# 20200614.net
KiCad netlist of a schematic drawn in Altium Designer
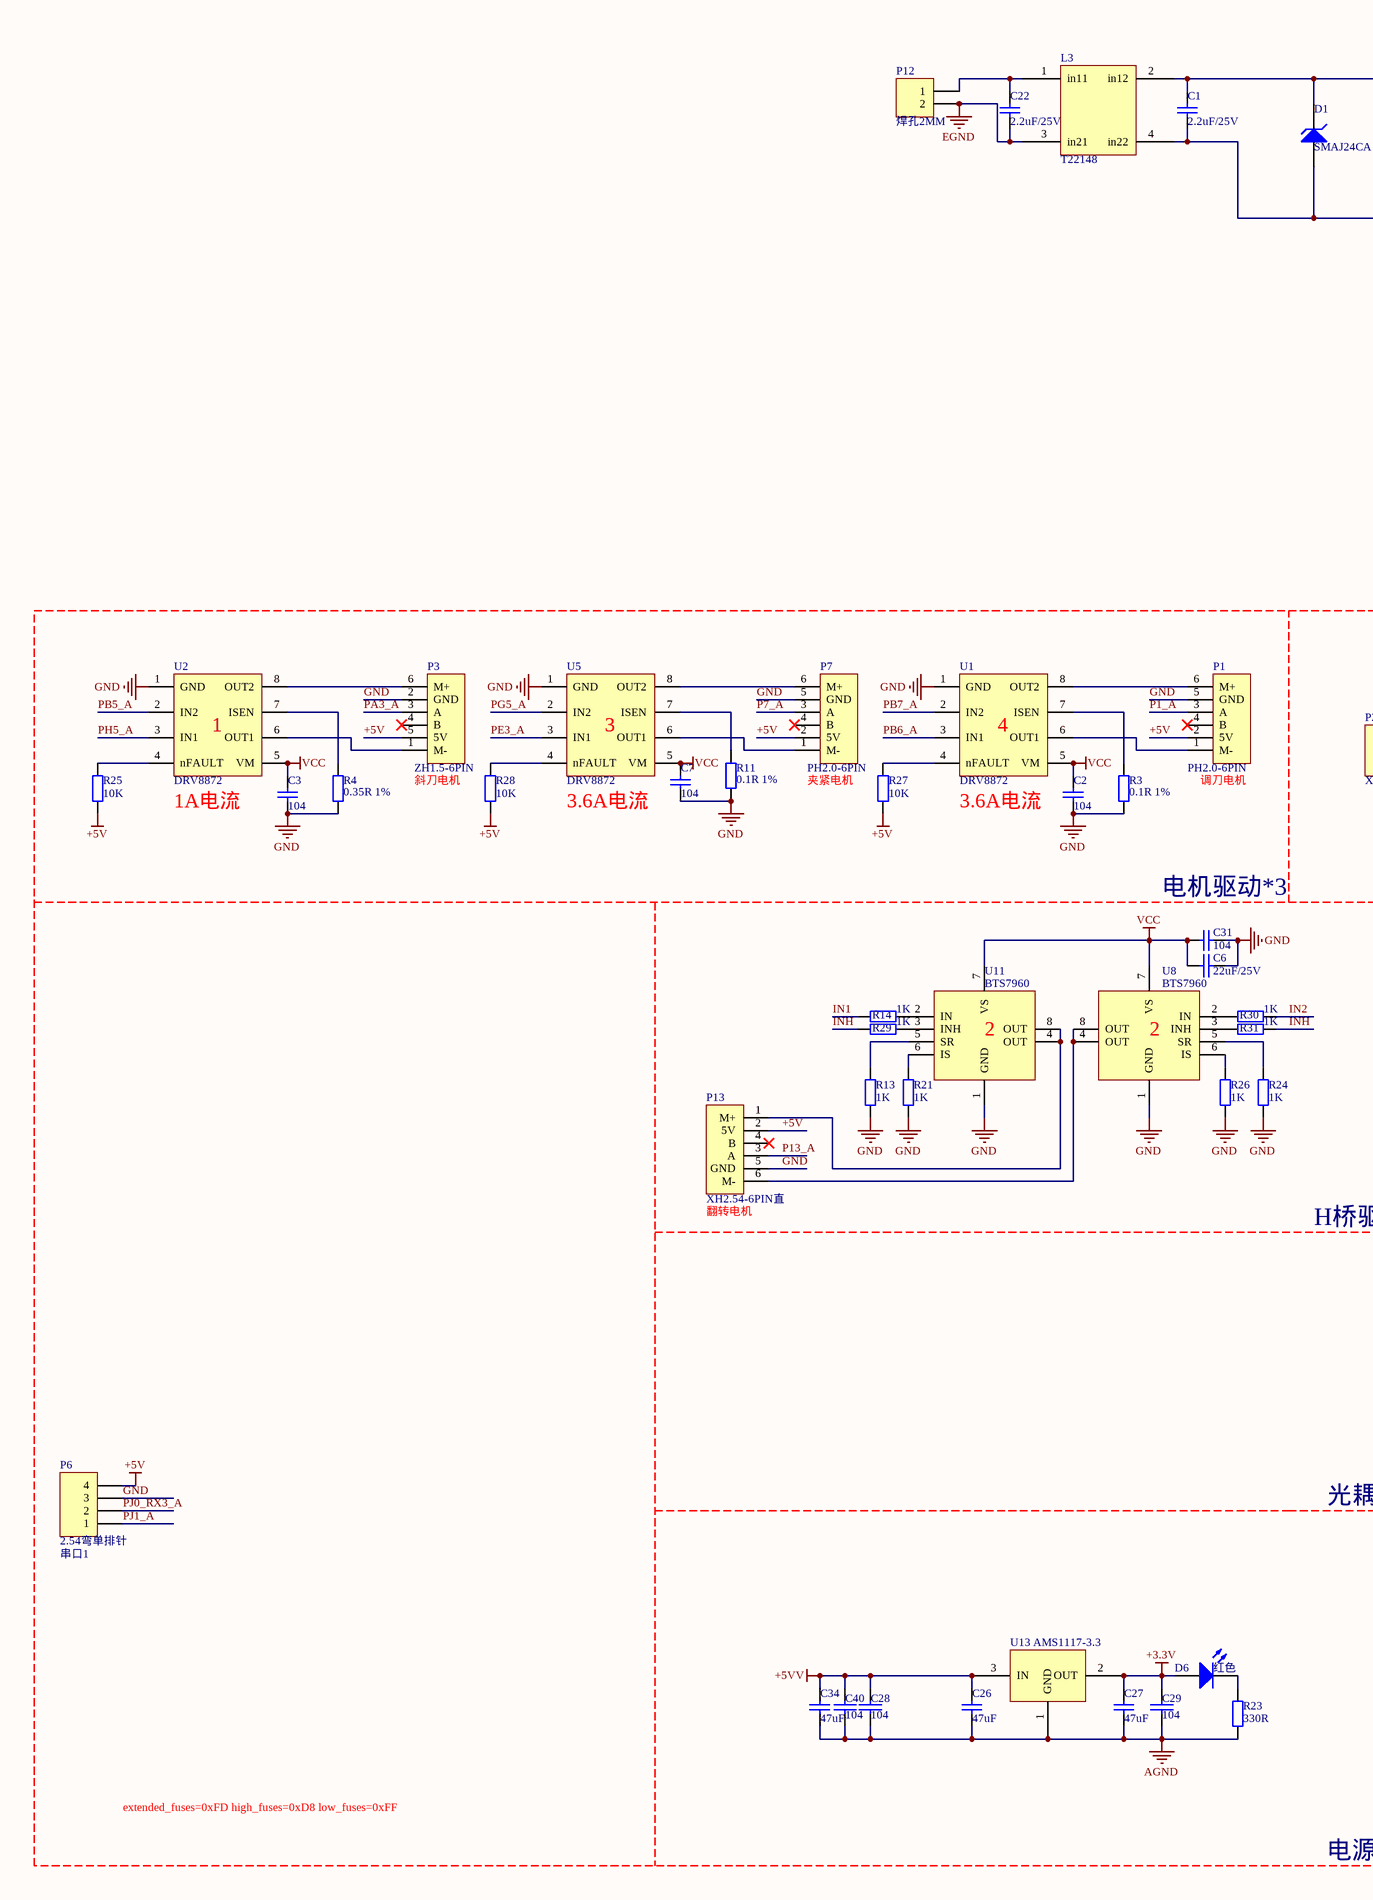
[diagram p0: 剥皮器20200614.SCHDOC, left]
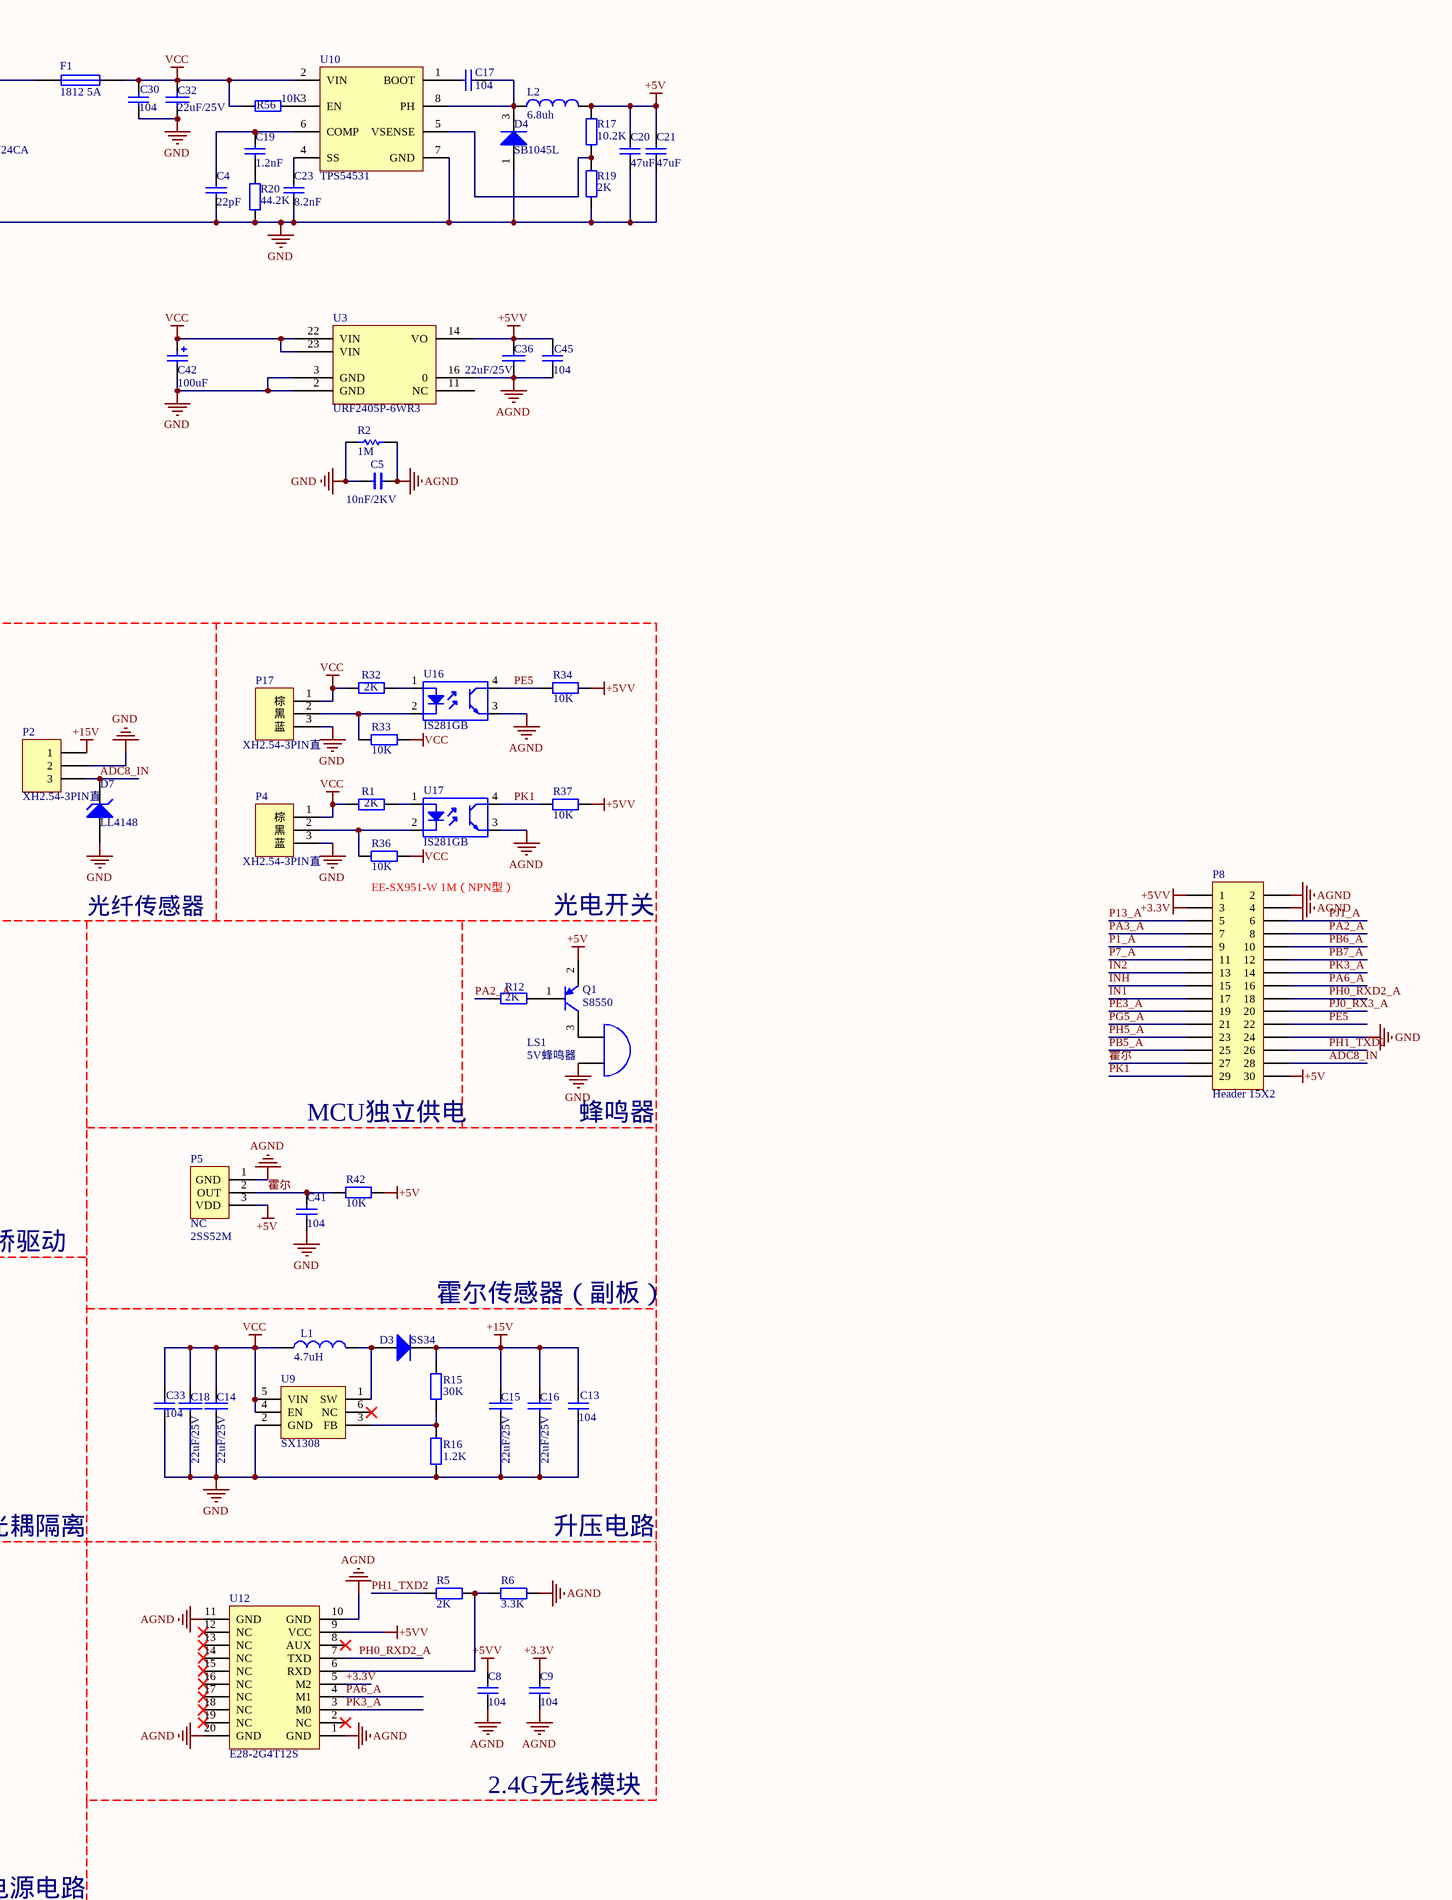
[diagram p1: 剥皮器20200614.SCHDOC, right]

(export (version "E")
  (design (tool "Eeschema 10.0.6"))
  (components
    (comp (ref "C1")
      (value "2.2uF/25V")
      (footprint "0805-C")
      (description "Capacitor")
      (fields (field (name "PUBLISHER") "Altium Limited"))
      (libsource (lib "Miscellaneous Devices") (part "Cap"))
    )
    (comp (ref "C2")
      (value "104")
      (footprint "0805-C")
      (description "Capacitor")
      (fields (field (name "PUBLISHER") "Altium Limited"))
      (libsource (lib "Miscellaneous Devices") (part "Cap"))
    )
    (comp (ref "C3")
      (value "104")
      (footprint "0805-C")
      (description "Capacitor")
      (fields (field (name "PUBLISHER") "Altium Limited"))
      (libsource (lib "Miscellaneous Devices") (part "Cap"))
    )
    (comp (ref "C4")
      (value "22pF")
      (footprint "0805-C")
      (description "Capacitor")
      (fields (field (name "PUBLISHER") "Altium Limited"))
      (libsource (lib "Miscellaneous Devices") (part "Cap"))
    )
    (comp (ref "C5")
      (value "10nF/2KV")
      (footprint "1206C")
      (description "C")
      (libsource (lib "Schlib_20110825") (part "C"))
    )
    (comp (ref "C6")
      (value "22uF/25V")
      (footprint "1206C")
      (description "Capacitor")
      (libsource (lib "*") (part "CAP"))
    )
    (comp (ref "C7")
      (value "104")
      (footprint "0805-C")
      (description "Capacitor")
      (fields (field (name "PUBLISHER") "Altium Limited"))
      (libsource (lib "Miscellaneous Devices") (part "Cap"))
    )
    (comp (ref "C8")
      (value "104")
      (footprint "0805-C")
      (description "Capacitor")
      (fields (field (name "PUBLISHER") "Altium Limited"))
      (libsource (lib "Miscellaneous Devices") (part "Cap"))
    )
    (comp (ref "C9")
      (value "104")
      (footprint "0805-C")
      (description "Capacitor")
      (fields (field (name "PUBLISHER") "Altium Limited"))
      (libsource (lib "Miscellaneous Devices") (part "Cap"))
    )
    (comp (ref "C13")
      (value "104")
      (footprint "0805-C")
      (description "Capacitor")
      (fields (field (name "PUBLISHER") "Altium Limited"))
      (libsource (lib "Miscellaneous Devices") (part "Cap"))
    )
    (comp (ref "C14")
      (value "22uF/25V")
      (footprint "1206-C")
      (description "Capacitor")
      (libsource (lib "*") (part "CAP"))
    )
    (comp (ref "C15")
      (value "22uF/25V")
      (footprint "1206-C")
      (description "Capacitor")
      (libsource (lib "*") (part "CAP"))
    )
    (comp (ref "C16")
      (value "22uF/25V")
      (footprint "1206-C")
      (description "Capacitor")
      (libsource (lib "*") (part "CAP"))
    )
    (comp (ref "C17")
      (value "104")
      (footprint "0805-C")
      (description "Capacitor")
      (fields (field (name "PUBLISHER") "Altium Limited"))
      (libsource (lib "Miscellaneous Devices") (part "Cap"))
    )
    (comp (ref "C18")
      (value "22uF/25V")
      (footprint "1206-C")
      (description "Capacitor")
      (libsource (lib "*") (part "CAP"))
    )
    (comp (ref "C19")
      (value "1.2nF")
      (footprint "0805-C")
      (description "Capacitor")
      (fields (field (name "PUBLISHER") "Altium Limited"))
      (libsource (lib "Miscellaneous Devices") (part "Cap"))
    )
    (comp (ref "C20")
      (value "47uF")
      (footprint "0805-C")
      (description "Capacitor")
      (fields (field (name "PUBLISHER") "Altium Limited"))
      (libsource (lib "Miscellaneous Devices") (part "Cap"))
    )
    (comp (ref "C21")
      (value "47uF")
      (footprint "0805-C")
      (description "Capacitor")
      (fields (field (name "PUBLISHER") "Altium Limited"))
      (libsource (lib "Miscellaneous Devices") (part "Cap"))
    )
    (comp (ref "C22")
      (value "2.2uF/25V")
      (footprint "0805-C")
      (description "Capacitor")
      (fields (field (name "PUBLISHER") "Altium Limited"))
      (libsource (lib "Miscellaneous Devices") (part "Cap"))
    )
    (comp (ref "C23")
      (value "8.2nF")
      (footprint "0805-C")
      (description "Capacitor")
      (fields (field (name "PUBLISHER") "Altium Limited"))
      (libsource (lib "Miscellaneous Devices") (part "Cap"))
    )
    (comp (ref "C26")
      (value "47uF")
      (footprint "0805-C")
      (description "Capacitor")
      (fields (field (name "PUBLISHER") "Altium Limited"))
      (libsource (lib "Miscellaneous Devices") (part "Cap"))
    )
    (comp (ref "C27")
      (value "47uF")
      (footprint "0805-C")
      (description "Capacitor")
      (fields (field (name "PUBLISHER") "Altium Limited"))
      (libsource (lib "Miscellaneous Devices") (part "Cap"))
    )
    (comp (ref "C28")
      (value "104")
      (footprint "0805-C")
      (description "Capacitor")
      (libsource (lib "*") (part "CAP"))
    )
    (comp (ref "C29")
      (value "104")
      (footprint "0805-C")
      (description "Capacitor")
      (libsource (lib "*") (part "CAP"))
    )
    (comp (ref "C30")
      (value "104")
      (footprint "0805-C")
      (description "Capacitor")
      (fields (field (name "PUBLISHER") "Altium Limited"))
      (libsource (lib "Miscellaneous Devices") (part "Cap"))
    )
    (comp (ref "C31")
      (value "104")
      (footprint "0805-C")
      (description "Capacitor")
      (fields (field (name "PUBLISHER") "Altium Limited"))
      (libsource (lib "Miscellaneous Devices") (part "Cap"))
    )
    (comp (ref "C32")
      (value "22uF/25V")
      (footprint "1206-C")
      (description "Capacitor")
      (libsource (lib "*") (part "CAP"))
    )
    (comp (ref "C33")
      (value "104")
      (footprint "0805-C")
      (description "Capacitor")
      (fields (field (name "PUBLISHER") "Altium Limited"))
      (libsource (lib "Miscellaneous Devices") (part "Cap"))
    )
    (comp (ref "C34")
      (value "47uF")
      (footprint "0805-C")
      (description "Capacitor")
      (fields (field (name "PUBLISHER") "Altium Limited"))
      (libsource (lib "Miscellaneous Devices") (part "Cap"))
    )
    (comp (ref "C36")
      (value "22uF/25V")
      (footprint "1206-C")
      (description "Capacitor")
      (libsource (lib "*") (part "CAP"))
    )
    (comp (ref "C40")
      (value "104")
      (footprint "0805-C")
      (description "Capacitor")
      (libsource (lib "*") (part "CAP"))
    )
    (comp (ref "C41")
      (value "104")
      (footprint "0805-C")
      (description "Capacitor")
      (fields (field (name "PUBLISHER") "Altium Limited"))
      (libsource (lib "Miscellaneous Devices") (part "Cap"))
    )
    (comp (ref "C42")
      (value "100uF")
      (footprint "LC-CASE-C_6032")
      (description "Polarized Capacitor (Axial)")
      (fields (field (name "PUBLISHER") "Altium Limited"))
      (libsource (lib "Miscellaneous Devices") (part "Cap Pol2"))
    )
    (comp (ref "C45")
      (value "104")
      (footprint "0805-C")
      (description "Capacitor")
      (fields (field (name "PUBLISHER") "Altium Limited"))
      (libsource (lib "Miscellaneous Devices") (part "Cap"))
    )
    (comp (ref "D1")
      (value "SMAJ24CA")
      (footprint "sma")
      (description "Zener Diode")
      (fields (field (name "PUBLISHER") "Altium Limited"))
      (libsource (lib "Miscellaneous Devices") (part "D Zener"))
    )
    (comp (ref "D3")
      (value "SS34")
      (footprint "SMA - JW")
      (description "1 Amp General Purpose Rectifier")
      (fields (field (name "PUBLISHER") "Altium Limited"))
      (libsource (lib "Miscellaneous Devices") (part "Diode 1N4007"))
    )
    (comp (ref "D4")
      (value "SB1045L")
      (footprint "TO-277")
      (description "1 Amp General Purpose Rectifier")
      (fields (field (name "PUBLISHER") "Altium Limited"))
      (libsource (lib "Miscellaneous Devices") (part "Diode 1N4001"))
    )
    (comp (ref "D6")
      (value "红色")
      (footprint "0805-LED")
      (description "Typical INFRARED GaAs LED")
      (fields (field (name "PUBLISHER") "Altium Limited"))
      (libsource (lib "Miscellaneous Devices") (part "LED0"))
    )
    (comp (ref "D7")
      (value "LL4148")
      (footprint "LC-LL-34")
      (description "Zener Diode")
      (fields (field (name "PUBLISHER") "Altium Limited"))
      (libsource (lib "Miscellaneous Devices") (part "D Zener"))
    )
    (comp (ref "F1")
      (value "1812 5A")
      (footprint "LC-1812_R")
      (description "Fuse")
      (fields (field (name "PUBLISHER") "Altium Limited"))
      (libsource (lib "Miscellaneous Devices") (part "Fuse 1"))
    )
    (comp (ref "L1")
      (value "4.7uH")
      (footprint "7*7*4电感")
      (description "Inductor")
      (fields (field (name "PUBLISHER") "Altium Limited"))
      (libsource (lib "Miscellaneous Devices") (part "Inductor"))
    )
    (comp (ref "L2")
      (value "6.8uh")
      (footprint "7*7*4电感")
      (description "Inductor")
      (fields (field (name "PUBLISHER") "Altium Limited"))
      (libsource (lib "Miscellaneous Devices") (part "Inductor"))
    )
    (comp (ref "L3") (value "T22148") (footprint "T181007") (libsource (lib "Schlib_20110825") (part "共模电感")))
    (comp (ref "LS1")
      (value "5V蜂鸣器")
      (footprint "蜂鸣器0905")
      (description "Electrical Bell")
      (fields (field (name "PUBLISHER") "Altium Limited"))
      (libsource (lib "Miscellaneous Devices") (part "Bell"))
    )
    (comp (ref "P1")
      (value "PH2.0-6PIN")
      (footprint "PH2.0-6PIN")
      (description "Header, 6-Pin")
      (fields (field (name "PUBLISHER") "Altium Limited"))
      (libsource (lib "") (part "Header 6_2"))
    )
    (comp (ref "P2")
      (value "XH2.54-3PIN直")
      (footprint "XH2.54-3PIN直")
      (description "Header, 3-Pin")
      (fields (field (name "PUBLISHER") "Altium Limited"))
      (libsource (lib "Miscellaneous Connectors") (part "Header 3"))
    )
    (comp (ref "P3")
      (value "ZH1.5-6PIN")
      (footprint "ZH1.5-6PIN")
      (description "Header, 6-Pin")
      (fields (field (name "PUBLISHER") "Altium Limited"))
      (libsource (lib "") (part "Header 6_1"))
    )
    (comp (ref "P4")
      (value "XH2.54-3PIN直")
      (footprint "XH2.54-3PIN直")
      (description "Header, 3-Pin")
      (fields (field (name "PUBLISHER") "Altium Limited"))
      (libsource (lib "") (part "Header 3_1"))
    )
    (comp (ref "P5")
      (value "NC")
      (footprint "2SS52M")
      (description "Header, 3-Pin")
      (fields (field (name "PUBLISHER") "2SS52M"))
      (libsource (lib "") (part "Header 3_2"))
    )
    (comp (ref "P6")
      (value "2.54弯单排针")
      (footprint "HDR1X4H")
      (description "Header, 4-Pin")
      (fields (field (name "ALTIUM_UNNAMED_1") "串口1") (field (name "PUBLISHER") "Altium Limited"))
      (libsource (lib "Miscellaneous Connectors") (part "Header 4"))
    )
    (comp (ref "P7")
      (value "PH2.0-6PIN")
      (footprint "PH2.0-6PIN")
      (description "Header, 6-Pin")
      (fields (field (name "PUBLISHER") "Altium Limited"))
      (libsource (lib "") (part "Header 6_2"))
    )
    (comp (ref "P8")
      (value "Header 15X2")
      (footprint "SIP15-1.27")
      (description "Header, 15-Pin, Dual row")
      (fields (field (name "PUBLISHER") "Altium Limited"))
      (libsource (lib "Miscellaneous Connectors") (part "Header 15X2"))
    )
    (comp (ref "P12")
      (value "焊孔2MM")
      (footprint "HDR1X2")
      (description "Header, 2-Pin")
      (fields (field (name "PUBLISHER") "Altium Limited"))
      (libsource (lib "Miscellaneous Connectors") (part "Header 2"))
    )
    (comp (ref "P13")
      (value "XH2.54-6PIN直")
      (footprint "XH2.54-6PIN直")
      (description "Header, 6-Pin")
      (fields (field (name "PUBLISHER") "Altium Limited"))
      (libsource (lib "Miscellaneous Connectors") (part "Header 6"))
    )
    (comp (ref "P17")
      (value "XH2.54-3PIN直")
      (footprint "XH2.54-3PIN直")
      (description "Header, 3-Pin")
      (fields (field (name "PUBLISHER") "Altium Limited"))
      (libsource (lib "") (part "Header 3_1"))
    )
    (comp (ref "Q1")
      (value "S8550")
      (footprint "SOT--23")
      (description "PNP General Purpose Amplifier")
      (fields (field (name "PUBLISHER") "Altium Limited"))
      (libsource (lib "Miscellaneous Devices") (part "2N3906"))
    )
    (comp (ref "R1")
      (value "2K")
      (footprint "0805-R")
      (description "Resistor")
      (fields (field (name "PUBLISHER") "Altium Limited"))
      (libsource (lib "Miscellaneous Devices") (part "Res2"))
    )
    (comp (ref "R2")
      (value "1M")
      (footprint "2512R")
      (description "Resistor")
      (fields (field (name "PUBLISHER") "Altium Limited"))
      (libsource (lib "Miscellaneous Devices") (part "Res1"))
    )
    (comp (ref "R3")
      (value "0.1R 1%")
      (footprint "2512-R")
      (description "Resistor")
      (fields (field (name "PUBLISHER") "Altium Limited"))
      (libsource (lib "") (part "Res2_2"))
    )
    (comp (ref "R4")
      (value "0.35R 1%")
      (footprint "2512-R")
      (description "Resistor")
      (fields (field (name "PUBLISHER") "Altium Limited"))
      (libsource (lib "") (part "Res2_2"))
    )
    (comp (ref "R5")
      (value "2K")
      (footprint "0805-R")
      (description "Resistor")
      (fields (field (name "PUBLISHER") "Altium Limited"))
      (libsource (lib "Miscellaneous Devices") (part "Res2"))
    )
    (comp (ref "R6")
      (value "3.3K")
      (footprint "0805-R")
      (description "Resistor")
      (fields (field (name "PUBLISHER") "Altium Limited"))
      (libsource (lib "Miscellaneous Devices") (part "Res2"))
    )
    (comp (ref "R11")
      (value "0.1R 1%")
      (footprint "2512-R")
      (description "Resistor")
      (fields (field (name "PUBLISHER") "Altium Limited"))
      (libsource (lib "") (part "Res2_2"))
    )
    (comp (ref "R12")
      (value "2K")
      (footprint "0805-R")
      (description "Resistor")
      (fields (field (name "PUBLISHER") "Altium Limited"))
      (libsource (lib "") (part "Res2_1"))
    )
    (comp (ref "R13")
      (value "1K")
      (footprint "0805-R")
      (description "Resistor")
      (fields (field (name "PUBLISHER") "Altium Limited"))
      (libsource (lib "") (part "Res2_2"))
    )
    (comp (ref "R14")
      (value "1K")
      (footprint "0805-R")
      (description "Resistor")
      (fields (field (name "PUBLISHER") "Altium Limited"))
      (libsource (lib "") (part "Res2_1"))
    )
    (comp (ref "R15")
      (value "30K")
      (footprint "0805-R")
      (description "Resistor")
      (fields (field (name "PUBLISHER") "Altium Limited"))
      (libsource (lib "") (part "Res2_3"))
    )
    (comp (ref "R16")
      (value "1.2K")
      (footprint "0805-R")
      (description "Resistor")
      (fields (field (name "PUBLISHER") "Altium Limited"))
      (libsource (lib "") (part "Res2_3"))
    )
    (comp (ref "R17")
      (value "10.2K")
      (footprint "0805-R")
      (description "Resistor")
      (fields (field (name "PUBLISHER") "Altium Limited"))
      (libsource (lib "") (part "Res2_2"))
    )
    (comp (ref "R19")
      (value "2K")
      (footprint "0805-R")
      (description "Resistor")
      (fields (field (name "PUBLISHER") "Altium Limited"))
      (libsource (lib "") (part "Res2_2"))
    )
    (comp (ref "R20")
      (value "44.2K")
      (footprint "0805-R")
      (description "Resistor")
      (fields (field (name "PUBLISHER") "Altium Limited"))
      (libsource (lib "") (part "Res2_2"))
    )
    (comp (ref "R21")
      (value "1K")
      (footprint "0805-R")
      (description "Resistor")
      (fields (field (name "PUBLISHER") "Altium Limited"))
      (libsource (lib "") (part "Res2_2"))
    )
    (comp (ref "R23")
      (value "330R")
      (footprint "0805-R")
      (description "Resistor")
      (fields (field (name "PUBLISHER") "Altium Limited"))
      (libsource (lib "") (part "Res2_3"))
    )
    (comp (ref "R24")
      (value "1K")
      (footprint "0805-R")
      (description "Resistor")
      (fields (field (name "PUBLISHER") "Altium Limited"))
      (libsource (lib "Miscellaneous Devices") (part "Res2"))
    )
    (comp (ref "R25")
      (value "10K")
      (footprint "0805-R")
      (description "Resistor")
      (fields (field (name "PUBLISHER") "Altium Limited"))
      (libsource (lib "") (part "Res2_2"))
    )
    (comp (ref "R26")
      (value "1K")
      (footprint "0805-R")
      (description "Resistor")
      (fields (field (name "PUBLISHER") "Altium Limited"))
      (libsource (lib "Miscellaneous Devices") (part "Res2"))
    )
    (comp (ref "R27")
      (value "10K")
      (footprint "0805-R")
      (description "Resistor")
      (fields (field (name "PUBLISHER") "Altium Limited"))
      (libsource (lib "") (part "Res2_2"))
    )
    (comp (ref "R28")
      (value "10K")
      (footprint "0805-R")
      (description "Resistor")
      (fields (field (name "PUBLISHER") "Altium Limited"))
      (libsource (lib "") (part "Res2_2"))
    )
    (comp (ref "R29")
      (value "1K")
      (footprint "0805-R")
      (description "Resistor")
      (fields (field (name "PUBLISHER") "Altium Limited"))
      (libsource (lib "") (part "Res2_1"))
    )
    (comp (ref "R30")
      (value "1K")
      (footprint "0805-R")
      (description "Resistor")
      (fields (field (name "PUBLISHER") "Altium Limited"))
      (libsource (lib "") (part "Res2_1"))
    )
    (comp (ref "R31")
      (value "1K")
      (footprint "0805-R")
      (description "Resistor")
      (fields (field (name "PUBLISHER") "Altium Limited"))
      (libsource (lib "") (part "Res2_1"))
    )
    (comp (ref "R32")
      (value "2K")
      (footprint "0805-R")
      (description "Resistor")
      (fields (field (name "PUBLISHER") "Altium Limited"))
      (libsource (lib "Miscellaneous Devices") (part "Res2"))
    )
    (comp (ref "R33")
      (value "10K")
      (footprint "0805-R")
      (description "Resistor")
      (fields (field (name "PUBLISHER") "Altium Limited"))
      (libsource (lib "") (part "Res2_1"))
    )
    (comp (ref "R34")
      (value "10K")
      (footprint "0805-R")
      (description "Resistor")
      (fields (field (name "PUBLISHER") "Altium Limited"))
      (libsource (lib "Miscellaneous Devices") (part "Res2"))
    )
    (comp (ref "R36")
      (value "10K")
      (footprint "0805-R")
      (description "Resistor")
      (fields (field (name "PUBLISHER") "Altium Limited"))
      (libsource (lib "") (part "Res2_1"))
    )
    (comp (ref "R37")
      (value "10K")
      (footprint "0805-R")
      (description "Resistor")
      (fields (field (name "PUBLISHER") "Altium Limited"))
      (libsource (lib "Miscellaneous Devices") (part "Res2"))
    )
    (comp (ref "R42")
      (value "10K")
      (footprint "0805-R")
      (description "Resistor")
      (fields (field (name "PUBLISHER") "Altium Limited"))
      (libsource (lib "") (part "Res2_1"))
    )
    (comp (ref "R56")
      (value "10K")
      (footprint "0805-R")
      (description "Resistor")
      (fields (field (name "PUBLISHER") "Altium Limited"))
      (libsource (lib "") (part "Res2_1"))
    )
    (comp (ref "U1")
      (value "DRV8872")
      (footprint "SOP-8带散热")
      (description "6N137")
      (libsource (lib "JW专用库") (part "6N137"))
    )
    (comp (ref "U2")
      (value "DRV8872")
      (footprint "SOP-8带散热")
      (description "6N137")
      (libsource (lib "JW专用库") (part "6N137"))
    )
    (comp (ref "U3")
      (value "URF2405P-6WR3")
      (footprint "URF2405P-6WR3")
      (libsource (lib "Schlib_20110825") (part "URF2405P-6WR3"))
    )
    (comp (ref "U5")
      (value "DRV8872")
      (footprint "SOP-8带散热")
      (description "6N137")
      (libsource (lib "JW专用库") (part "6N137"))
    )
    (comp (ref "U8") (value "BTS7960") (footprint "LC-TO-263-7") (libsource (lib "") (part "BTS7960_1")))
    (comp (ref "U9") (value "SX1308") (footprint "SOT-23-6") (libsource (lib "JW专用库") (part "SX1308")))
    (comp (ref "U10") (value "TPS54531") (footprint "SOP-8带散热") (libsource (lib "*") (part "TPS54531")))
    (comp (ref "U11") (value "BTS7960") (footprint "LC-TO-263-7") (libsource (lib "*") (part "BTS7960")))
    (comp (ref "U12")
      (value "E28-2G4T12S")
      (footprint "E28-2G4T12S")
      (libsource (lib "JW专用元件库") (part "E43-433T13S"))
    )
    (comp (ref "U13") (value "AMS1117-3.3") (footprint "SOT--223") (libsource (lib "*") (part "AS1117")))
    (comp (ref "U16") (value "IS281GB") (footprint "LC-SOP-4_P1.27") (libsource (lib "*") (part "TLP521-1")))
    (comp (ref "U17") (value "IS281GB") (footprint "LC-SOP-4_P1.27") (libsource (lib "*") (part "TLP521-1")))
  )
  (nets
    (net (code "1") (name "+3.3V") (class "Default")
      (node (ref "C27") (pin "2") (pinfunction "2_2") (pintype "passive"))
      (node (ref "C29") (pin "1") (pinfunction "1_1") (pintype "passive"))
      (node (ref "C9") (pin "1") (pinfunction "1_1") (pintype "passive"))
      (node (ref "D6") (pin "1") (pinfunction "A_1") (pintype "passive"))
      (node (ref "P8") (pin "3") (pinfunction "3_3") (pintype "passive"))
      (node (ref "U12") (pin "5") (pinfunction "M2_5") (pintype "passive"))
      (node (ref "U13") (pin "2") (pinfunction "OUT_2") (pintype "passive"))
    )
    (net (code "2") (name "+5V") (class "Default")
      (node (ref "C20") (pin "2") (pinfunction "2_2") (pintype "passive"))
      (node (ref "C21") (pin "2") (pinfunction "2_2") (pintype "passive"))
      (node (ref "L2") (pin "2") (pinfunction "2_2") (pintype "passive"))
      (node (ref "P1") (pin "2") (pinfunction "5V_2") (pintype "passive"))
      (node (ref "P13") (pin "2") (pinfunction "5V_2") (pintype "passive"))
      (node (ref "P3") (pin "5") (pinfunction "5V_5") (pintype "passive"))
      (node (ref "P5") (pin "3") (pinfunction "VDD_3") (pintype "passive"))
      (node (ref "P6") (pin "4") (pinfunction "4_4") (pintype "passive"))
      (node (ref "P7") (pin "2") (pinfunction "5V_2") (pintype "passive"))
      (node (ref "P8") (pin "30") (pinfunction "30_30") (pintype "passive"))
      (node (ref "Q1") (pin "2") (pinfunction "E_2") (pintype "passive"))
      (node (ref "R17") (pin "2") (pinfunction "2_2") (pintype "passive"))
      (node (ref "R25") (pin "1") (pinfunction "1_1") (pintype "passive"))
      (node (ref "R27") (pin "1") (pinfunction "1_1") (pintype "passive"))
      (node (ref "R28") (pin "1") (pinfunction "1_1") (pintype "passive"))
      (node (ref "R42") (pin "1") (pinfunction "1_1") (pintype "passive"))
    )
    (net (code "3") (name "+5VV") (class "Default")
      (node (ref "C26") (pin "2") (pinfunction "2_2") (pintype "passive"))
      (node (ref "C28") (pin "1") (pinfunction "1_1") (pintype "passive"))
      (node (ref "C34") (pin "2") (pinfunction "2_2") (pintype "passive"))
      (node (ref "C36") (pin "1") (pinfunction "1_1") (pintype "passive"))
      (node (ref "C40") (pin "1") (pinfunction "1_1") (pintype "passive"))
      (node (ref "C45") (pin "2") (pinfunction "2_2") (pintype "passive"))
      (node (ref "C8") (pin "1") (pinfunction "1_1") (pintype "passive"))
      (node (ref "P8") (pin "1") (pinfunction "1_1") (pintype "passive"))
      (node (ref "R34") (pin "2") (pinfunction "2_2") (pintype "passive"))
      (node (ref "R37") (pin "2") (pinfunction "2_2") (pintype "passive"))
      (node (ref "U12") (pin "9") (pinfunction "VCC_9") (pintype "passive"))
      (node (ref "U13") (pin "3") (pinfunction "IN_3") (pintype "passive"))
      (node (ref "U3") (pin "14") (pinfunction "VO_14") (pintype "passive"))
    )
    (net (code "4") (name "+15V") (class "Default")
      (node (ref "C13") (pin "1") (pinfunction "1_1") (pintype "passive"))
      (node (ref "C15") (pin "1") (pinfunction "1_1") (pintype "passive"))
      (node (ref "C16") (pin "1") (pinfunction "1_1") (pintype "passive"))
      (node (ref "D3") (pin "2") (pinfunction "K_2") (pintype "passive"))
      (node (ref "P2") (pin "1") (pinfunction "1_1") (pintype "passive"))
      (node (ref "R15") (pin "1") (pinfunction "1_1") (pintype "passive"))
    )
    (net (code "5") (name "/ADC8_IN") (class "Default")
      (node (ref "D7") (pin "2") (pinfunction "K_2") (pintype "passive"))
      (node (ref "P2") (pin "3") (pinfunction "3_3") (pintype "passive"))
      (node (ref "P8") (pin "28") (pinfunction "28_28") (pintype "passive"))
    )
    (net (code "6") (name "/IN1") (class "Default")
      (node (ref "P8") (pin "17") (pinfunction "17_17") (pintype "passive"))
      (node (ref "R14") (pin "2") (pinfunction "2_2") (pintype "passive"))
    )
    (net (code "7") (name "/IN2") (class "Default")
      (node (ref "P8") (pin "13") (pinfunction "13_13") (pintype "passive"))
      (node (ref "R30") (pin "1") (pinfunction "1_1") (pintype "passive"))
    )
    (net (code "8") (name "/INH") (class "Default")
      (node (ref "P8") (pin "15") (pinfunction "15_15") (pintype "passive"))
      (node (ref "R29") (pin "2") (pinfunction "2_2") (pintype "passive"))
      (node (ref "R31") (pin "1") (pinfunction "1_1") (pintype "passive"))
    )
    (net (code "9") (name "/P1_A") (class "Default")
      (node (ref "P1") (pin "3") (pinfunction "A_3") (pintype "passive"))
      (node (ref "P8") (pin "9") (pinfunction "9_9") (pintype "passive"))
    )
    (net (code "10") (name "/P7_A") (class "Default")
      (node (ref "P7") (pin "3") (pinfunction "A_3") (pintype "passive"))
      (node (ref "P8") (pin "11") (pinfunction "11_11") (pintype "passive"))
    )
    (net (code "11") (name "/P13_A") (class "Default")
      (node (ref "P13") (pin "3") (pinfunction "A_3") (pintype "passive"))
      (node (ref "P8") (pin "5") (pinfunction "5_5") (pintype "passive"))
    )
    (net (code "12") (name "/PA2_A") (class "Default")
      (node (ref "P8") (pin "8") (pinfunction "8_8") (pintype "passive"))
      (node (ref "R12") (pin "2") (pinfunction "2_2") (pintype "passive"))
    )
    (net (code "13") (name "/PA3_A") (class "Default")
      (node (ref "P3") (pin "3") (pinfunction "A_3") (pintype "passive"))
      (node (ref "P8") (pin "7") (pinfunction "7_7") (pintype "passive"))
    )
    (net (code "14") (name "/PA6_A") (class "Default")
      (node (ref "P8") (pin "16") (pinfunction "16_16") (pintype "passive"))
      (node (ref "U12") (pin "4") (pinfunction "M1_4") (pintype "passive"))
    )
    (net (code "15") (name "/PB5_A") (class "Default")
      (node (ref "P8") (pin "25") (pinfunction "25_25") (pintype "passive"))
      (node (ref "U2") (pin "2") (pinfunction "IN2_2") (pintype "passive"))
    )
    (net (code "16") (name "/PB6_A") (class "Default")
      (node (ref "P8") (pin "10") (pinfunction "10_10") (pintype "passive"))
      (node (ref "U1") (pin "3") (pinfunction "IN1_3") (pintype "passive"))
    )
    (net (code "17") (name "/PB7_A") (class "Default")
      (node (ref "P8") (pin "12") (pinfunction "12_12") (pintype "passive"))
      (node (ref "U1") (pin "2") (pinfunction "IN2_2") (pintype "passive"))
    )
    (net (code "18") (name "/PE3_A") (class "Default")
      (node (ref "P8") (pin "19") (pinfunction "19_19") (pintype "passive"))
      (node (ref "U5") (pin "3") (pinfunction "IN1_3") (pintype "passive"))
    )
    (net (code "19") (name "/PE5") (class "Default")
      (node (ref "P8") (pin "22") (pinfunction "22_22") (pintype "passive"))
      (node (ref "R34") (pin "1") (pinfunction "1_1") (pintype "passive"))
      (node (ref "U16") (pin "4") (pinfunction "4_4") (pintype "passive"))
    )
    (net (code "20") (name "/PG5_A") (class "Default")
      (node (ref "P8") (pin "21") (pinfunction "21_21") (pintype "passive"))
      (node (ref "U5") (pin "2") (pinfunction "IN2_2") (pintype "passive"))
    )
    (net (code "21") (name "/PH0_RXD2_A") (class "Default")
      (node (ref "P8") (pin "18") (pinfunction "18_18") (pintype "passive"))
      (node (ref "U12") (pin "7") (pinfunction "TXD_7") (pintype "passive"))
    )
    (net (code "22") (name "/PH1_TXD2") (class "Default")
      (node (ref "P8") (pin "26") (pinfunction "26_26") (pintype "passive"))
      (node (ref "R5") (pin "1") (pinfunction "1_1") (pintype "passive"))
    )
    (net (code "23") (name "/PH5_A") (class "Default")
      (node (ref "P8") (pin "23") (pinfunction "23_23") (pintype "passive"))
      (node (ref "U2") (pin "3") (pinfunction "IN1_3") (pintype "passive"))
    )
    (net (code "24") (name "/PJ0_RX3_A") (class "Default")
      (node (ref "P6") (pin "2") (pinfunction "2_2") (pintype "passive"))
      (node (ref "P8") (pin "20") (pinfunction "20_20") (pintype "passive"))
    )
    (net (code "25") (name "/PJ1_A") (class "Default")
      (node (ref "P6") (pin "1") (pinfunction "1_1") (pintype "passive"))
      (node (ref "P8") (pin "6") (pinfunction "6_6") (pintype "passive"))
    )
    (net (code "26") (name "/PK1") (class "Default")
      (node (ref "P8") (pin "29") (pinfunction "29_29") (pintype "passive"))
      (node (ref "R37") (pin "1") (pinfunction "1_1") (pintype "passive"))
      (node (ref "U17") (pin "4") (pinfunction "4_4") (pintype "passive"))
    )
    (net (code "27") (name "/PK3_A") (class "Default")
      (node (ref "P8") (pin "14") (pinfunction "14_14") (pintype "passive"))
      (node (ref "U12") (pin "3") (pinfunction "M0_3") (pintype "passive"))
    )
    (net (code "28") (name "/霍尔") (class "Default")
      (node (ref "C41") (pin "1") (pinfunction "1_1") (pintype "passive"))
      (node (ref "P5") (pin "2") (pinfunction "OUT_2") (pintype "passive"))
      (node (ref "P8") (pin "27") (pinfunction "27_27") (pintype "passive"))
      (node (ref "R42") (pin "2") (pinfunction "2_2") (pintype "passive"))
    )
    (net (code "29") (name "AGND") (class "Default")
      (node (ref "C26") (pin "1") (pinfunction "1_1") (pintype "passive"))
      (node (ref "C27") (pin "1") (pinfunction "1_1") (pintype "passive"))
      (node (ref "C28") (pin "2") (pinfunction "2_2") (pintype "passive"))
      (node (ref "C29") (pin "2") (pinfunction "2_2") (pintype "passive"))
      (node (ref "C34") (pin "1") (pinfunction "1_1") (pintype "passive"))
      (node (ref "C36") (pin "2") (pinfunction "2_2") (pintype "passive"))
      (node (ref "C40") (pin "2") (pinfunction "2_2") (pintype "passive"))
      (node (ref "C45") (pin "1") (pinfunction "1_1") (pintype "passive"))
      (node (ref "C5") (pin "1") (pintype "passive"))
      (node (ref "C8") (pin "2") (pinfunction "2_2") (pintype "passive"))
      (node (ref "C9") (pin "2") (pinfunction "2_2") (pintype "passive"))
      (node (ref "P5") (pin "1") (pinfunction "GND_1") (pintype "passive"))
      (node (ref "P8") (pin "2") (pinfunction "2_2") (pintype "passive"))
      (node (ref "P8") (pin "4") (pinfunction "4_4") (pintype "passive"))
      (node (ref "R2") (pin "1") (pinfunction "1_1") (pintype "passive"))
      (node (ref "R23") (pin "2") (pinfunction "2_2") (pintype "passive"))
      (node (ref "R6") (pin "2") (pinfunction "2_2") (pintype "passive"))
      (node (ref "U12") (pin "1") (pinfunction "GND_1") (pintype "passive"))
      (node (ref "U12") (pin "10") (pinfunction "GND_10") (pintype "passive"))
      (node (ref "U12") (pin "11") (pinfunction "GND_11") (pintype "passive"))
      (node (ref "U12") (pin "20") (pinfunction "GND_20") (pintype "passive"))
      (node (ref "U13") (pin "1") (pinfunction "GND_1") (pintype "passive"))
      (node (ref "U16") (pin "3") (pinfunction "3_3") (pintype "passive"))
      (node (ref "U17") (pin "3") (pinfunction "3_3") (pintype "passive"))
      (node (ref "U3") (pin "16") (pinfunction "0_16") (pintype "passive"))
    )
    (net (code "30") (name "EGND") (class "Default")
      (node (ref "C22") (pin "2") (pinfunction "2_2") (pintype "passive"))
      (node (ref "L3") (pin "3") (pinfunction "in21_3") (pintype "passive"))
      (node (ref "P12") (pin "2") (pinfunction "2_2") (pintype "passive"))
    )
    (net (code "31") (name "GND") (class "Default")
      (node (ref "C1") (pin "2") (pinfunction "2_2") (pintype "passive"))
      (node (ref "C13") (pin "2") (pinfunction "2_2") (pintype "passive"))
      (node (ref "C14") (pin "2") (pinfunction "2_2") (pintype "passive"))
      (node (ref "C15") (pin "2") (pinfunction "2_2") (pintype "passive"))
      (node (ref "C16") (pin "2") (pinfunction "2_2") (pintype "passive"))
      (node (ref "C18") (pin "2") (pinfunction "2_2") (pintype "passive"))
      (node (ref "C2") (pin "2") (pinfunction "2_2") (pintype "passive"))
      (node (ref "C20") (pin "1") (pinfunction "1_1") (pintype "passive"))
      (node (ref "C21") (pin "1") (pinfunction "1_1") (pintype "passive"))
      (node (ref "C23") (pin "2") (pinfunction "2_2") (pintype "passive"))
      (node (ref "C3") (pin "2") (pinfunction "2_2") (pintype "passive"))
      (node (ref "C30") (pin "1") (pinfunction "1_1") (pintype "passive"))
      (node (ref "C31") (pin "2") (pinfunction "2_2") (pintype "passive"))
      (node (ref "C32") (pin "2") (pinfunction "2_2") (pintype "passive"))
      (node (ref "C33") (pin "1") (pinfunction "1_1") (pintype "passive"))
      (node (ref "C4") (pin "2") (pinfunction "2_2") (pintype "passive"))
      (node (ref "C41") (pin "2") (pinfunction "2_2") (pintype "passive"))
      (node (ref "C42") (pin "2") (pinfunction "2_2") (pintype "passive"))
      (node (ref "C5") (pin "2") (pintype "passive"))
      (node (ref "C6") (pin "2") (pinfunction "2_2") (pintype "passive"))
      (node (ref "C7") (pin "2") (pinfunction "2_2") (pintype "passive"))
      (node (ref "D1") (pin "1") (pinfunction "A_1") (pintype "passive"))
      (node (ref "D4") (pin "1") (pinfunction "A_1") (pintype "passive"))
      (node (ref "D7") (pin "1") (pinfunction "A_1") (pintype "passive"))
      (node (ref "L3") (pin "4") (pinfunction "in22_4") (pintype "passive"))
      (node (ref "LS1") (pin "2") (pinfunction "B_2") (pintype "passive"))
      (node (ref "P1") (pin "5") (pinfunction "GND_5") (pintype "passive"))
      (node (ref "P13") (pin "5") (pinfunction "GND_5") (pintype "passive"))
      (node (ref "P17") (pin "3") (pinfunction "蓝_3") (pintype "passive"))
      (node (ref "P2") (pin "2") (pinfunction "2_2") (pintype "passive"))
      (node (ref "P3") (pin "2") (pinfunction "GND_2") (pintype "passive"))
      (node (ref "P4") (pin "3") (pinfunction "蓝_3") (pintype "passive"))
      (node (ref "P6") (pin "3") (pinfunction "3_3") (pintype "passive"))
      (node (ref "P7") (pin "5") (pinfunction "GND_5") (pintype "passive"))
      (node (ref "P8") (pin "24") (pinfunction "24_24") (pintype "passive"))
      (node (ref "R11") (pin "1") (pinfunction "1_1") (pintype "passive"))
      (node (ref "R13") (pin "1") (pinfunction "1_1") (pintype "passive"))
      (node (ref "R16") (pin "2") (pinfunction "2_2") (pintype "passive"))
      (node (ref "R19") (pin "1") (pinfunction "1_1") (pintype "passive"))
      (node (ref "R2") (pin "2") (pinfunction "2_2") (pintype "passive"))
      (node (ref "R20") (pin "1") (pinfunction "1_1") (pintype "passive"))
      (node (ref "R21") (pin "1") (pinfunction "1_1") (pintype "passive"))
      (node (ref "R24") (pin "1") (pinfunction "1_1") (pintype "passive"))
      (node (ref "R26") (pin "1") (pinfunction "1_1") (pintype "passive"))
      (node (ref "R3") (pin "1") (pinfunction "1_1") (pintype "passive"))
      (node (ref "R4") (pin "1") (pinfunction "1_1") (pintype "passive"))
      (node (ref "U1") (pin "1") (pinfunction "GND_1") (pintype "passive"))
      (node (ref "U10") (pin "7") (pinfunction "GND_7") (pintype "passive"))
      (node (ref "U11") (pin "1") (pinfunction "GND_1") (pintype "passive"))
      (node (ref "U2") (pin "1") (pinfunction "GND_1") (pintype "passive"))
      (node (ref "U3") (pin "2") (pinfunction "GND_2") (pintype "passive"))
      (node (ref "U3") (pin "3") (pinfunction "GND_3") (pintype "passive"))
      (node (ref "U5") (pin "1") (pinfunction "GND_1") (pintype "passive"))
      (node (ref "U8") (pin "1") (pinfunction "GND_1") (pintype "passive"))
      (node (ref "U9") (pin "2") (pinfunction "GND_2") (pintype "passive"))
    )
    (net (code "32") (name "Net-(C19-Pad2)") (class "Default")
      (node (ref "C19") (pin "2") (pinfunction "2_2") (pintype "passive"))
      (node (ref "R20") (pin "2") (pinfunction "2_2") (pintype "passive"))
    )
    (net (code "33") (name "Net-(D1-K)") (class "Default")
      (node (ref "C1") (pin "1") (pinfunction "1_1") (pintype "passive"))
      (node (ref "D1") (pin "2") (pinfunction "K_2") (pintype "passive"))
      (node (ref "F1") (pin "2") (pinfunction "2_2") (pintype "passive"))
      (node (ref "L3") (pin "2") (pinfunction "in12_2") (pintype "passive"))
    )
    (net (code "34") (name "Net-(D3-A)") (class "Default")
      (node (ref "D3") (pin "1") (pinfunction "A_1") (pintype "passive"))
      (node (ref "L1") (pin "2") (pinfunction "2_2") (pintype "passive"))
      (node (ref "U9") (pin "1") (pinfunction "SW_1") (pintype "passive"))
    )
    (net (code "35") (name "Net-(D4-K)") (class "Default")
      (node (ref "C17") (pin "2") (pinfunction "2_2") (pintype "passive"))
      (node (ref "D4") (pin "3") (pinfunction "K_3") (pintype "passive"))
      (node (ref "L2") (pin "1") (pinfunction "1_1") (pintype "passive"))
      (node (ref "U10") (pin "8") (pinfunction "PH_8") (pintype "passive"))
    )
    (net (code "36") (name "Net-(D6-K)") (class "Default")
      (node (ref "D6") (pin "2") (pinfunction "K_2") (pintype "passive"))
      (node (ref "R23") (pin "1") (pinfunction "1_1") (pintype "passive"))
    )
    (net (code "37") (name "Net-(L3-in11)") (class "Default")
      (node (ref "C22") (pin "1") (pinfunction "1_1") (pintype "passive"))
      (node (ref "L3") (pin "1") (pinfunction "in11_1") (pintype "passive"))
      (node (ref "P12") (pin "1") (pinfunction "1_1") (pintype "passive"))
    )
    (net (code "38") (name "Net-(LS1-A)") (class "Default")
      (node (ref "LS1") (pin "1") (pinfunction "A_1") (pintype "passive"))
      (node (ref "Q1") (pin "3") (pinfunction "C_3") (pintype "passive"))
    )
    (net (code "39") (name "Net-(P1-M+)") (class "Default")
      (node (ref "P1") (pin "6") (pinfunction "M+_6") (pintype "passive"))
      (node (ref "U1") (pin "8") (pinfunction "OUT2_8") (pintype "passive"))
    )
    (net (code "40") (name "Net-(P1-M-)") (class "Default")
      (node (ref "P1") (pin "1") (pinfunction "M-_1") (pintype "passive"))
      (node (ref "U1") (pin "6") (pinfunction "OUT1_6") (pintype "passive"))
    )
    (net (code "41") (name "Net-(P3-M+)") (class "Default")
      (node (ref "P3") (pin "6") (pinfunction "M+_6") (pintype "passive"))
      (node (ref "U2") (pin "8") (pinfunction "OUT2_8") (pintype "passive"))
    )
    (net (code "42") (name "Net-(P3-M-)") (class "Default")
      (node (ref "P3") (pin "1") (pinfunction "M-_1") (pintype "passive"))
      (node (ref "U2") (pin "6") (pinfunction "OUT1_6") (pintype "passive"))
    )
    (net (code "43") (name "Net-(P4-黑)") (class "Default")
      (node (ref "P4") (pin "2") (pinfunction "黑_2") (pintype "passive"))
      (node (ref "R36") (pin "2") (pinfunction "2_2") (pintype "passive"))
      (node (ref "U17") (pin "2") (pinfunction "2_2") (pintype "passive"))
    )
    (net (code "44") (name "Net-(P7-M+)") (class "Default")
      (node (ref "P7") (pin "6") (pinfunction "M+_6") (pintype "passive"))
      (node (ref "U5") (pin "8") (pinfunction "OUT2_8") (pintype "passive"))
    )
    (net (code "45") (name "Net-(P7-M-)") (class "Default")
      (node (ref "P7") (pin "1") (pinfunction "M-_1") (pintype "passive"))
      (node (ref "U5") (pin "6") (pinfunction "OUT1_6") (pintype "passive"))
    )
    (net (code "46") (name "Net-(P13-M+)") (class "Default")
      (node (ref "P13") (pin "1") (pinfunction "M+_1") (pintype "passive"))
      (node (ref "U11") (pin "4") (pinfunction "OUT_4") (pintype "passive"))
      (node (ref "U11") (pin "8") (pinfunction "OUT_8") (pintype "passive"))
    )
    (net (code "47") (name "Net-(P13-M-)") (class "Default")
      (node (ref "P13") (pin "6") (pinfunction "M-_6") (pintype "passive"))
      (node (ref "U8") (pin "4") (pinfunction "OUT_4") (pintype "passive"))
      (node (ref "U8") (pin "8") (pinfunction "OUT_8") (pintype "passive"))
    )
    (net (code "48") (name "Net-(P17-黑)") (class "Default")
      (node (ref "P17") (pin "2") (pinfunction "黑_2") (pintype "passive"))
      (node (ref "R33") (pin "2") (pinfunction "2_2") (pintype "passive"))
      (node (ref "U16") (pin "2") (pinfunction "2_2") (pintype "passive"))
    )
    (net (code "49") (name "Net-(Q1-B)") (class "Default")
      (node (ref "Q1") (pin "1") (pinfunction "B_1") (pintype "passive"))
      (node (ref "R12") (pin "1") (pinfunction "1_1") (pintype "passive"))
    )
    (net (code "50") (name "Net-(R1-Pad2)") (class "Default")
      (node (ref "R1") (pin "2") (pinfunction "2_2") (pintype "passive"))
      (node (ref "U17") (pin "1") (pinfunction "1_1") (pintype "passive"))
    )
    (net (code "51") (name "Net-(R32-Pad2)") (class "Default")
      (node (ref "R32") (pin "2") (pinfunction "2_2") (pintype "passive"))
      (node (ref "U16") (pin "1") (pinfunction "1_1") (pintype "passive"))
    )
    (net (code "52") (name "Net-(U1-ISEN)") (class "Default")
      (node (ref "R3") (pin "2") (pinfunction "2_2") (pintype "passive"))
      (node (ref "U1") (pin "7") (pinfunction "ISEN_7") (pintype "passive"))
    )
    (net (code "53") (name "Net-(U1-nFAULT)") (class "Default")
      (node (ref "R27") (pin "2") (pinfunction "2_2") (pintype "passive"))
      (node (ref "U1") (pin "4") (pinfunction "nFAULT_4") (pintype "passive"))
    )
    (net (code "54") (name "Net-(U2-ISEN)") (class "Default")
      (node (ref "R4") (pin "2") (pinfunction "2_2") (pintype "passive"))
      (node (ref "U2") (pin "7") (pinfunction "ISEN_7") (pintype "passive"))
    )
    (net (code "55") (name "Net-(U2-nFAULT)") (class "Default")
      (node (ref "R25") (pin "2") (pinfunction "2_2") (pintype "passive"))
      (node (ref "U2") (pin "4") (pinfunction "nFAULT_4") (pintype "passive"))
    )
    (net (code "56") (name "Net-(U5-ISEN)") (class "Default")
      (node (ref "R11") (pin "2") (pinfunction "2_2") (pintype "passive"))
      (node (ref "U5") (pin "7") (pinfunction "ISEN_7") (pintype "passive"))
    )
    (net (code "57") (name "Net-(U5-nFAULT)") (class "Default")
      (node (ref "R28") (pin "2") (pinfunction "2_2") (pintype "passive"))
      (node (ref "U5") (pin "4") (pinfunction "nFAULT_4") (pintype "passive"))
    )
    (net (code "58") (name "Net-(U8-IN)") (class "Default")
      (node (ref "R30") (pin "2") (pinfunction "2_2") (pintype "passive"))
      (node (ref "U8") (pin "2") (pinfunction "IN_2") (pintype "passive"))
    )
    (net (code "59") (name "Net-(U8-INH)") (class "Default")
      (node (ref "R31") (pin "2") (pinfunction "2_2") (pintype "passive"))
      (node (ref "U8") (pin "3") (pinfunction "INH_3") (pintype "passive"))
    )
    (net (code "60") (name "Net-(U8-IS)") (class "Default")
      (node (ref "R26") (pin "2") (pinfunction "2_2") (pintype "passive"))
      (node (ref "U8") (pin "6") (pinfunction "IS_6") (pintype "passive"))
    )
    (net (code "61") (name "Net-(U8-SR)") (class "Default")
      (node (ref "R24") (pin "2") (pinfunction "2_2") (pintype "passive"))
      (node (ref "U8") (pin "5") (pinfunction "SR_5") (pintype "passive"))
    )
    (net (code "62") (name "Net-(U9-FB)") (class "Default")
      (node (ref "R15") (pin "2") (pinfunction "2_2") (pintype "passive"))
      (node (ref "R16") (pin "1") (pinfunction "1_1") (pintype "passive"))
      (node (ref "U9") (pin "3") (pinfunction "FB_3") (pintype "passive"))
    )
    (net (code "63") (name "Net-(U10-BOOT)") (class "Default")
      (node (ref "C17") (pin "1") (pinfunction "1_1") (pintype "passive"))
      (node (ref "U10") (pin "1") (pinfunction "BOOT_1") (pintype "passive"))
    )
    (net (code "64") (name "Net-(U10-COMP)") (class "Default")
      (node (ref "C19") (pin "1") (pinfunction "1_1") (pintype "passive"))
      (node (ref "C4") (pin "1") (pinfunction "1_1") (pintype "passive"))
      (node (ref "U10") (pin "6") (pinfunction "COMP_6") (pintype "passive"))
    )
    (net (code "65") (name "Net-(U10-EN)") (class "Default")
      (node (ref "R56") (pin "1") (pinfunction "1_1") (pintype "passive"))
      (node (ref "U10") (pin "3") (pinfunction "EN_3") (pintype "passive"))
    )
    (net (code "66") (name "Net-(U10-SS)") (class "Default")
      (node (ref "C23") (pin "1") (pinfunction "1_1") (pintype "passive"))
      (node (ref "U10") (pin "4") (pinfunction "SS_4") (pintype "passive"))
    )
    (net (code "67") (name "Net-(U10-VSENSE)") (class "Default")
      (node (ref "R17") (pin "1") (pinfunction "1_1") (pintype "passive"))
      (node (ref "R19") (pin "2") (pinfunction "2_2") (pintype "passive"))
      (node (ref "U10") (pin "5") (pinfunction "VSENSE_5") (pintype "passive"))
    )
    (net (code "68") (name "Net-(U11-IN)") (class "Default")
      (node (ref "R14") (pin "1") (pinfunction "1_1") (pintype "passive"))
      (node (ref "U11") (pin "2") (pinfunction "IN_2") (pintype "passive"))
    )
    (net (code "69") (name "Net-(U11-INH)") (class "Default")
      (node (ref "R29") (pin "1") (pinfunction "1_1") (pintype "passive"))
      (node (ref "U11") (pin "3") (pinfunction "INH_3") (pintype "passive"))
    )
    (net (code "70") (name "Net-(U11-IS)") (class "Default")
      (node (ref "R21") (pin "2") (pinfunction "2_2") (pintype "passive"))
      (node (ref "U11") (pin "6") (pinfunction "IS_6") (pintype "passive"))
    )
    (net (code "71") (name "Net-(U11-SR)") (class "Default")
      (node (ref "R13") (pin "2") (pinfunction "2_2") (pintype "passive"))
      (node (ref "U11") (pin "5") (pinfunction "SR_5") (pintype "passive"))
    )
    (net (code "72") (name "Net-(U12-RXD)") (class "Default")
      (node (ref "R5") (pin "2") (pinfunction "2_2") (pintype "passive"))
      (node (ref "R6") (pin "1") (pinfunction "1_1") (pintype "passive"))
      (node (ref "U12") (pin "6") (pinfunction "RXD_6") (pintype "passive"))
    )
    (net (code "73") (name "VCC") (class "Default")
      (node (ref "C14") (pin "1") (pinfunction "1_1") (pintype "passive"))
      (node (ref "C18") (pin "1") (pinfunction "1_1") (pintype "passive"))
      (node (ref "C2") (pin "1") (pinfunction "1_1") (pintype "passive"))
      (node (ref "C3") (pin "1") (pinfunction "1_1") (pintype "passive"))
      (node (ref "C30") (pin "2") (pinfunction "2_2") (pintype "passive"))
      (node (ref "C31") (pin "1") (pinfunction "1_1") (pintype "passive"))
      (node (ref "C32") (pin "1") (pinfunction "1_1") (pintype "passive"))
      (node (ref "C33") (pin "2") (pinfunction "2_2") (pintype "passive"))
      (node (ref "C42") (pin "1") (pinfunction "1_1") (pintype "passive"))
      (node (ref "C6") (pin "1") (pinfunction "1_1") (pintype "passive"))
      (node (ref "C7") (pin "1") (pinfunction "1_1") (pintype "passive"))
      (node (ref "F1") (pin "1") (pinfunction "1_1") (pintype "passive"))
      (node (ref "L1") (pin "1") (pinfunction "1_1") (pintype "passive"))
      (node (ref "P17") (pin "1") (pinfunction "棕_1") (pintype "passive"))
      (node (ref "P4") (pin "1") (pinfunction "棕_1") (pintype "passive"))
      (node (ref "R1") (pin "1") (pinfunction "1_1") (pintype "passive"))
      (node (ref "R32") (pin "1") (pinfunction "1_1") (pintype "passive"))
      (node (ref "R33") (pin "1") (pinfunction "1_1") (pintype "passive"))
      (node (ref "R36") (pin "1") (pinfunction "1_1") (pintype "passive"))
      (node (ref "R56") (pin "2") (pinfunction "2_2") (pintype "passive"))
      (node (ref "U1") (pin "5") (pinfunction "VM_5") (pintype "passive"))
      (node (ref "U10") (pin "2") (pinfunction "VIN_2") (pintype "passive"))
      (node (ref "U11") (pin "7") (pinfunction "VS_7") (pintype "passive"))
      (node (ref "U2") (pin "5") (pinfunction "VM_5") (pintype "passive"))
      (node (ref "U3") (pin "22") (pinfunction "VIN_22") (pintype "passive"))
      (node (ref "U3") (pin "23") (pinfunction "VIN_23") (pintype "passive"))
      (node (ref "U5") (pin "5") (pinfunction "VM_5") (pintype "passive"))
      (node (ref "U8") (pin "7") (pinfunction "VS_7") (pintype "passive"))
      (node (ref "U9") (pin "4") (pinfunction "EN_4") (pintype "passive"))
      (node (ref "U9") (pin "5") (pinfunction "VIN_5") (pintype "passive"))
    )
    (net (code "74") (name "unconnected-(P1-B-Pad4)") (class "Default")
      (node (ref "P1") (pin "4") (pinfunction "B_4") (pintype "passive+no_connect"))
    )
    (net (code "75") (name "unconnected-(P3-B-Pad4)") (class "Default")
      (node (ref "P3") (pin "4") (pinfunction "B_4") (pintype "passive+no_connect"))
    )
    (net (code "76") (name "unconnected-(P7-B-Pad4)") (class "Default")
      (node (ref "P7") (pin "4") (pinfunction "B_4") (pintype "passive+no_connect"))
    )
    (net (code "77") (name "unconnected-(P13-B-Pad4)") (class "Default")
      (node (ref "P13") (pin "4") (pinfunction "B_4") (pintype "passive+no_connect"))
    )
    (net (code "78") (name "unconnected-(U3-NC-Pad11)") (class "Default")
      (node (ref "U3") (pin "11") (pinfunction "NC_11") (pintype "passive"))
    )
    (net (code "79") (name "unconnected-(U9-NC-Pad6)") (class "Default")
      (node (ref "U9") (pin "6") (pinfunction "NC_6") (pintype "passive+no_connect"))
    )
    (net (code "80") (name "unconnected-(U12-AUX-Pad8)") (class "Default")
      (node (ref "U12") (pin "8") (pinfunction "AUX_8") (pintype "passive+no_connect"))
    )
    (net (code "81") (name "unconnected-(U12-NC-Pad2)") (class "Default")
      (node (ref "U12") (pin "2") (pinfunction "NC_2") (pintype "passive+no_connect"))
    )
    (net (code "82") (name "unconnected-(U12-NC-Pad12)") (class "Default")
      (node (ref "U12") (pin "12") (pinfunction "NC_12") (pintype "passive+no_connect"))
    )
    (net (code "83") (name "unconnected-(U12-NC-Pad13)") (class "Default")
      (node (ref "U12") (pin "13") (pinfunction "NC_13") (pintype "passive+no_connect"))
    )
    (net (code "84") (name "unconnected-(U12-NC-Pad14)") (class "Default")
      (node (ref "U12") (pin "14") (pinfunction "NC_14") (pintype "passive+no_connect"))
    )
    (net (code "85") (name "unconnected-(U12-NC-Pad15)") (class "Default")
      (node (ref "U12") (pin "15") (pinfunction "NC_15") (pintype "passive+no_connect"))
    )
    (net (code "86") (name "unconnected-(U12-NC-Pad16)") (class "Default")
      (node (ref "U12") (pin "16") (pinfunction "NC_16") (pintype "passive+no_connect"))
    )
    (net (code "87") (name "unconnected-(U12-NC-Pad17)") (class "Default")
      (node (ref "U12") (pin "17") (pinfunction "NC_17") (pintype "passive+no_connect"))
    )
    (net (code "88") (name "unconnected-(U12-NC-Pad18)") (class "Default")
      (node (ref "U12") (pin "18") (pinfunction "NC_18") (pintype "passive+no_connect"))
    )
    (net (code "89") (name "unconnected-(U12-NC-Pad19)") (class "Default")
      (node (ref "U12") (pin "19") (pinfunction "NC_19") (pintype "passive+no_connect"))
    )
  )
)
